# FULL_CB_Plugs_REV_C.net
KiCad netlist of a schematic drawn in Altium Designer
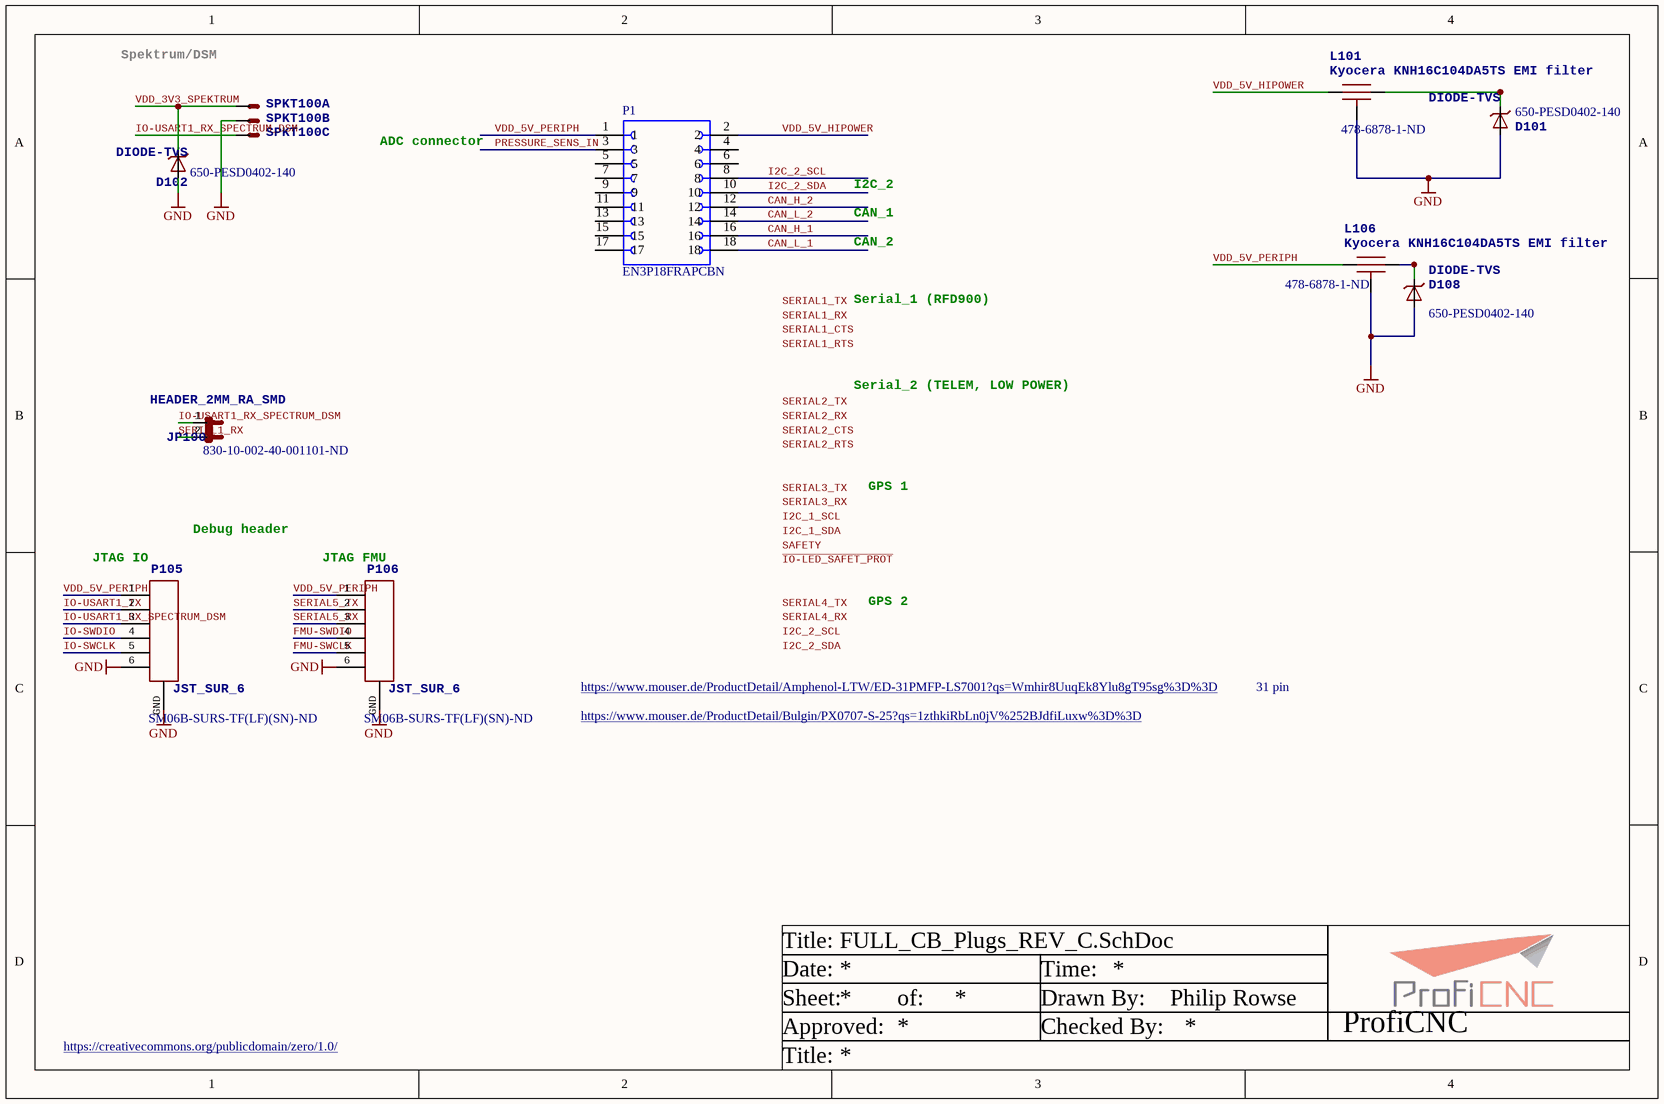
[diagram p0: FULL_CB_Plugs_REV_C.SchDoc]

(export (version "E")
  (design (tool "Eeschema 10.0.6"))
  (components
    (comp (ref "D101")
      (value "DIODE-TVS")
      (footprint "0402-TVS")
      (description "Diode, TVS, 14VWM, 40VC, 0402, SMD")
      (fields (field (name "SUPPLIER PART NUMBER 1") "650-PESD0402-140"))
      (libsource (lib "CB_REV_C") (part "DIODE-TVS"))
    )
    (comp (ref "D102")
      (value "DIODE-TVS")
      (footprint "0402-TVS")
      (description "Diode, TVS, 14VWM, 40VC, 0402, SMD")
      (fields (field (name "SUPPLIER PART NUMBER 1") "650-PESD0402-140"))
      (libsource (lib "CB_REV_C") (part "DIODE-TVS"))
    )
    (comp (ref "D108")
      (value "DIODE-TVS")
      (footprint "0402-TVS")
      (description "Diode, TVS, 14VWM, 40VC, 0402, SMD")
      (fields (field (name "SUPPLIER PART NUMBER 1") "650-PESD0402-140"))
      (libsource (lib "CB_REV_C") (part "DIODE-TVS"))
    )
    (comp (ref "JP100")
      (value "HEADER_2MM_RA_SMD")
      (footprint "HEADER_2MM_RA_2")
      (description "Connector, PCB, 2MM, 2Pos, R/A, SMD, Au")
      (fields (field (name "SUPPLIER PART NUMBER 1") "830-10-002-40-001101-ND"))
      (libsource (lib "CB_REV_C") (part "HEADER_2MM_RA_SMD"))
    )
    (comp (ref "L101")
      (value "Kyocera KNH16C104DA5TS EMI filter")
      (footprint "KYOCERA-KNH16-DA")
      (description "Capacitor, Filter, 0.1uF, 25V, 2A, 0603, SMD")
      (fields (field (name "SUPPLIER PART NUMBER 1") "478-6878-1-ND"))
      (libsource (lib "CB_REV_C") (part "KNH16C104DA5TS"))
    )
    (comp (ref "L106")
      (value "Kyocera KNH16C104DA5TS EMI filter")
      (footprint "KYOCERA-KNH16-DA")
      (description "Capacitor, Filter, 0.1uF, 25V, 2A, 0603, SMD")
      (fields (field (name "SUPPLIER PART NUMBER 1") "478-6878-1-ND"))
      (libsource (lib "CB_REV_C") (part "KNH16C104DA5TS"))
    )
    (comp (ref "P1")
      (value "EN3P18FRAPCBN")
      (footprint "SWITCHCRAFT_EN3P18FRAPCBN")
      (libsource (lib "CB_REV_C") (part "EN3P18FRAPCBN"))
    )
    (comp (ref "P105")
      (value "JST_SUR_6")
      (footprint "JST_SUR_H6")
      (description "Connector, Header, 6Pos, .8mm IDC, R/A, SMD, Tin")
      (fields (field (name "SUPPLIER PART NUMBER 1") "SM06B-SURS-TF(LF)(SN)-ND"))
      (libsource (lib "CB_REV_C") (part "JST_SUR_6"))
    )
    (comp (ref "P106")
      (value "JST_SUR_6")
      (footprint "JST_SUR_H6")
      (description "Connector, Header, 6Pos, .8mm IDC, R/A, SMD, Tin")
      (fields (field (name "SUPPLIER PART NUMBER 1") "SM06B-SURS-TF(LF)(SN)-ND"))
      (libsource (lib "CB_REV_C") (part "JST_SUR_6"))
    )
    (comp (ref "SPKT100")
      (value "CONN_SPEKTRUM_RX-TH")
      (footprint "B3B-ZR")
      (description "Spektrum RX connector; JST ZH series S3B-ZR-SM4A-TF")
      (fields (field (name "PARTNO") "B3B-ZR(LF)(SN)"))
      (libsource (lib "CB_REV_C") (part "CONN_SPEKTRUM_RX-TH"))
    )
  )
  (nets
    (net (code "1") (name "/CAN_H_1") (class "Default")
      (node (ref "P1") (pin "16") (pinfunction "16_16") (pintype "passive"))
    )
    (net (code "2") (name "/CAN_H_2") (class "Default")
      (node (ref "P1") (pin "12") (pinfunction "12_12") (pintype "passive"))
    )
    (net (code "3") (name "/CAN_L_1") (class "Default")
      (node (ref "P1") (pin "18") (pinfunction "18_18") (pintype "passive"))
    )
    (net (code "4") (name "/CAN_L_2") (class "Default")
      (node (ref "P1") (pin "14") (pinfunction "14_14") (pintype "passive"))
    )
    (net (code "5") (name "/FMU-SWCLK") (class "Default")
      (node (ref "P106") (pin "5") (pinfunction "5_5") (pintype "passive"))
    )
    (net (code "6") (name "/FMU-SWDIO") (class "Default")
      (node (ref "P106") (pin "4") (pinfunction "4_4") (pintype "passive"))
    )
    (net (code "9") (name "/I2C_2_SCL") (class "Default")
      (node (ref "P1") (pin "8") (pinfunction "8_8") (pintype "passive"))
    )
    (net (code "10") (name "/I2C_2_SDA") (class "Default")
      (node (ref "P1") (pin "10") (pinfunction "10_10") (pintype "passive"))
    )
    (net (code "11") (name "/IO-SWCLK") (class "Default")
      (node (ref "P105") (pin "5") (pinfunction "5_5") (pintype "passive"))
    )
    (net (code "12") (name "/IO-SWDIO") (class "Default")
      (node (ref "P105") (pin "4") (pinfunction "4_4") (pintype "passive"))
    )
    (net (code "13") (name "/IO-USART1_RX_SPECTRUM_DSM") (class "Default")
      (node (ref "JP100") (pin "1") (pinfunction "1_1") (pintype "passive"))
      (node (ref "P105") (pin "3") (pinfunction "3_3") (pintype "passive"))
      (node (ref "SPKT100") (pin "1") (pinfunction "S_1") (pintype "passive"))
    )
    (net (code "14") (name "/IO-USART1_TX") (class "Default")
      (node (ref "P105") (pin "2") (pinfunction "2_2") (pintype "passive"))
    )
    (net (code "15") (name "/PRESSURE_SENS_IN") (class "Default")
      (node (ref "P1") (pin "3") (pinfunction "3_3") (pintype "passive"))
    )
    (net (code "19") (name "/SERIAL1_RX") (class "Default")
      (node (ref "JP100") (pin "2") (pinfunction "2_2") (pintype "passive"))
    )
    (net (code "29") (name "/SERIAL5_RX") (class "Default")
      (node (ref "P106") (pin "3") (pinfunction "3_3") (pintype "passive"))
    )
    (net (code "30") (name "/SERIAL5_TX") (class "Default")
      (node (ref "P106") (pin "2") (pinfunction "2_2") (pintype "passive"))
    )
    (net (code "31") (name "/VDD_3V3_SPEKTRUM") (class "Default")
      (node (ref "D102") (pin "C") (pinfunction "C_C") (pintype "passive"))
      (node (ref "SPKT100") (pin "3") (pinfunction "S_3") (pintype "passive"))
    )
    (net (code "32") (name "/VDD_5V_HIPOWER") (class "Default")
      (node (ref "L101") (pin "P$1") (pinfunction "P$1_P$1") (pintype "passive"))
      (node (ref "P1") (pin "2") (pinfunction "2_2") (pintype "passive"))
    )
    (net (code "33") (name "/VDD_5V_PERIPH") (class "Default")
      (node (ref "L106") (pin "P$1") (pinfunction "P$1_P$1") (pintype "passive"))
      (node (ref "P1") (pin "1") (pinfunction "1_1") (pintype "passive"))
      (node (ref "P105") (pin "1") (pinfunction "1_1") (pintype "passive"))
      (node (ref "P106") (pin "1") (pinfunction "1_1") (pintype "passive"))
    )
    (net (code "35") (name "GND") (class "Default")
      (node (ref "D101") (pin "A") (pinfunction "A_A") (pintype "passive"))
      (node (ref "D102") (pin "A") (pinfunction "A_A") (pintype "passive"))
      (node (ref "D108") (pin "A") (pinfunction "A_A") (pintype "passive"))
      (node (ref "L101") (pin "GND") (pinfunction "GND_GND") (pintype "passive"))
      (node (ref "L106") (pin "GND") (pinfunction "GND_GND") (pintype "passive"))
      (node (ref "P105") (pin "6") (pinfunction "6_6") (pintype "passive"))
      (node (ref "P105") (pin "GND") (pinfunction "GND_GND") (pintype "passive"))
      (node (ref "P106") (pin "6") (pinfunction "6_6") (pintype "passive"))
      (node (ref "P106") (pin "GND") (pinfunction "GND_GND") (pintype "passive"))
      (node (ref "SPKT100") (pin "2") (pinfunction "S_2") (pintype "passive"))
    )
    (net (code "36") (name "Net-(D101-PadC)") (class "Default")
      (node (ref "D101") (pin "C") (pinfunction "C_C") (pintype "passive"))
      (node (ref "L101") (pin "P$2") (pinfunction "P$2_P$2") (pintype "passive"))
    )
    (net (code "37") (name "Net-(D108-PadC)") (class "Default")
      (node (ref "D108") (pin "C") (pinfunction "C_C") (pintype "passive"))
      (node (ref "L106") (pin "P$2") (pinfunction "P$2_P$2") (pintype "passive"))
    )
    (net (code "38") (name "unconnected-(P1-Pad4)") (class "Default")
      (node (ref "P1") (pin "4") (pinfunction "4_4") (pintype "passive"))
    )
    (net (code "39") (name "unconnected-(P1-Pad5)") (class "Default")
      (node (ref "P1") (pin "5") (pinfunction "5_5") (pintype "passive"))
    )
    (net (code "40") (name "unconnected-(P1-Pad6)") (class "Default")
      (node (ref "P1") (pin "6") (pinfunction "6_6") (pintype "passive"))
    )
    (net (code "41") (name "unconnected-(P1-Pad7)") (class "Default")
      (node (ref "P1") (pin "7") (pinfunction "7_7") (pintype "passive"))
    )
    (net (code "42") (name "unconnected-(P1-Pad9)") (class "Default")
      (node (ref "P1") (pin "9") (pinfunction "9_9") (pintype "passive"))
    )
    (net (code "43") (name "unconnected-(P1-Pad11)") (class "Default")
      (node (ref "P1") (pin "11") (pinfunction "11_11") (pintype "passive"))
    )
    (net (code "44") (name "unconnected-(P1-Pad13)") (class "Default")
      (node (ref "P1") (pin "13") (pinfunction "13_13") (pintype "passive"))
    )
    (net (code "45") (name "unconnected-(P1-Pad15)") (class "Default")
      (node (ref "P1") (pin "15") (pinfunction "15_15") (pintype "passive"))
    )
    (net (code "46") (name "unconnected-(P1-Pad17)") (class "Default")
      (node (ref "P1") (pin "17") (pinfunction "17_17") (pintype "passive"))
    )
  )
)
